# power_circuit_v4_down.net
KiCad netlist of a schematic drawn in EAGLE
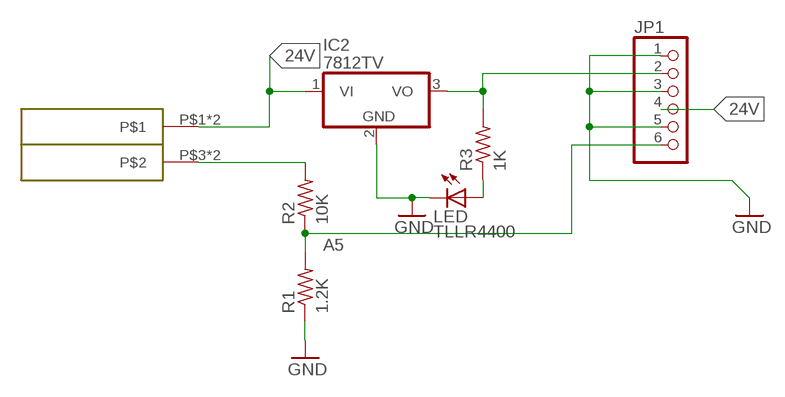
[diagram p0: schematic, sheet 1]

(export (version "E")
  (design (tool "Eeschema 10.0.6"))
  (components
    (comp (ref "IC2")
      (value "7812TV")
      (footprint "eagle-import:TO220V")
      (libsource (lib "eagle-import") (part "78TV12"))
    )
    (comp (ref "JP1")
      (value "PINHD-1X6B")
      (footprint "eagle-import:1X06-BIG")
      (libsource (lib "eagle-import") (part "PINHD-1X6B"))
    )
    (comp (ref "LED")
      (value "TLLR4400")
      (footprint "eagle-import:LED3MM")
      (fields (field (name "MF") "VISHAY SEMICONDUCTOR"))
      (libsource (lib "eagle-import") (part "TLLR4400"))
    )
    (comp (ref "R1")
      (value "1.2K")
      (footprint "eagle-import:0207_5V")
      (libsource (lib "eagle-import") (part "R-US_0207/5V"))
    )
    (comp (ref "R2")
      (value "10K")
      (footprint "eagle-import:0207_5V")
      (libsource (lib "eagle-import") (part "R-US_0207/5V"))
    )
    (comp (ref "R3")
      (value "1K")
      (footprint "eagle-import:0207_5V")
      (libsource (lib "eagle-import") (part "R-US_0207/5V"))
    )
    (comp (ref "U$1")
      (value "MY-PLUG")
      (footprint "eagle-import:CON-SEG")
      (libsource (lib "eagle-import") (part "MY-PLUG"))
    )
  )
  (nets
    (net (code "1") (name "/A5") (class "Default")
      (node (ref "JP1") (pin "6") (pinfunction "6_6") (pintype "passive"))
      (node (ref "R1") (pin "2") (pinfunction "2_2") (pintype "passive"))
      (node (ref "R2") (pin "1") (pinfunction "1_1") (pintype "passive"))
    )
    (net (code "2") (name "24V") (class "Default")
      (node (ref "IC2") (pin "1") (pinfunction "VI_1") (pintype "input"))
      (node (ref "JP1") (pin "4") (pinfunction "4_4") (pintype "passive"))
      (node (ref "U$1") (pin "P$1") (pinfunction "P$1_P$1") (pintype "bidirectional"))
      (node (ref "U$1") (pin "P$2") (pinfunction "P$1_P$2") (pintype "bidirectional"))
    )
    (net (code "3") (name "GND") (class "Default")
      (node (ref "IC2") (pin "2") (pinfunction "GND_2") (pintype "passive"))
      (node (ref "JP1") (pin "1") (pinfunction "1_1") (pintype "passive"))
      (node (ref "JP1") (pin "3") (pinfunction "3_3") (pintype "passive"))
      (node (ref "JP1") (pin "5") (pinfunction "5_5") (pintype "passive"))
      (node (ref "LED") (pin "K") (pinfunction "C_K") (pintype "passive"))
      (node (ref "R1") (pin "1") (pinfunction "1_1") (pintype "passive"))
    )
    (net (code "4") (name "Net-(IC2-VO)") (class "Default")
      (node (ref "IC2") (pin "3") (pinfunction "VO_3") (pintype "passive"))
      (node (ref "JP1") (pin "2") (pinfunction "2_2") (pintype "passive"))
      (node (ref "R3") (pin "2") (pinfunction "2_2") (pintype "passive"))
    )
    (net (code "5") (name "Net-(LED-PadA)") (class "Default")
      (node (ref "LED") (pin "A") (pinfunction "A_A") (pintype "passive"))
      (node (ref "R3") (pin "1") (pinfunction "1_1") (pintype "passive"))
    )
    (net (code "6") (name "Net-(R2-Pad2)") (class "Default")
      (node (ref "R2") (pin "2") (pinfunction "2_2") (pintype "passive"))
      (node (ref "U$1") (pin "P$3") (pinfunction "P$2_P$3") (pintype "bidirectional"))
      (node (ref "U$1") (pin "P$4") (pinfunction "P$2_P$4") (pintype "bidirectional"))
    )
  )
)
